# LTM8074neg_PA.net
KiCad netlist of a schematic drawn in Altium Designer
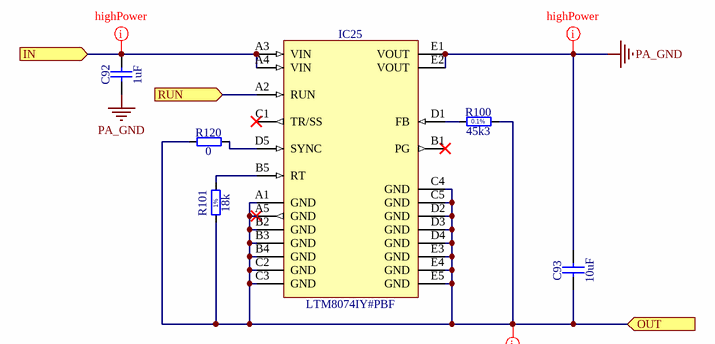
[diagram p0: LTM8074neg_PA.SchDoc]

(export (version "E")
  (design (tool "Eeschema 10.0.6"))
  (components
    (comp (ref "C92")
      (value "1uF")
      (footprint "CAPC2012X110N")
      (description "Non-polarised capacitor")
      (fields
        (field (name "PART NUMBER") "CC0805_1UF_50V_10%_X7R")
        (field (name "VOLTAGE") "50V")
        (field (name "AUTHOR") "CERN DEM JLC")
      )
      (libsource (lib "Capacitors") (part "Capacitor - non polarized"))
    )
    (comp (ref "C93")
      (value "10uF")
      (footprint "CAPC2012X95N")
      (description "Non-polarised capacitor")
      (fields
        (field (name "PART NUMBER") "CC0805_10UF_25V_10%_X5R")
        (field (name "VOLTAGE") "25V")
        (field (name "AUTHOR") "CERN DEM JLC")
      )
      (libsource (lib "Capacitors") (part "Capacitor - non polarized"))
    )
    (comp (ref "IC25")
      (value "LTM8074IY#PBF")
      (footprint "BGA25C65P5X5_400X400X198")
      (description "40VIN, 1.2A Silent Switcher µModule Regulator")
      (fields (field (name "MANUFACTURER") "LINEAR TECHNOLOGY") (field (name "AUTHOR") "CERN DEM JLC"))
      (libsource (lib "ICs And Semiconductors") (part "LTM8074"))
    )
    (comp (ref "R100")
      (value "45k3")
      (footprint "RESC1608X55N")
      (description "Resistor - 0.1%")
      (fields
        (field (name "PART NUMBER") "R0603_45K3_0.1%_0.063W_10PPM")
        (field (name "POWER") "0.063W")
        (field (name "AUTHOR") "CERN DEM JLC")
      )
      (libsource (lib "Resistors") (part "Resistor - 0.1%"))
    )
    (comp (ref "R101")
      (value "18k")
      (footprint "RESC1608X55N")
      (description "Resistor - 1%")
      (fields
        (field (name "PART NUMBER") "R0603_18K_1%_0.1W_100PPM")
        (field (name "POWER") "0.1W")
        (field (name "AUTHOR") "CERN DEM JLC")
      )
      (libsource (lib "Resistors") (part "Resistor - 1%"))
    )
    (comp (ref "R120")
      (value "0")
      (footprint "RESC1608X55N")
      (description "Resistor")
      (fields
        (field (name "PART NUMBER") "R0603_0R_JUMPER")
        (field (name "MANUFACTURER") "GENERIC")
        (field (name "AUTHOR") "CERN DEM JLC")
      )
      (libsource (lib "Resistors") (part "Resistor"))
    )
  )
  (nets
    (net (code "1") (name "/IN") (class "Default")
      (node (ref "C92") (pin "2") (pinfunction "2_2") (pintype "passive"))
      (node (ref "IC25") (pin "A3") (pinfunction "VIN_A3") (pintype "input"))
      (node (ref "IC25") (pin "A4") (pinfunction "VIN_A4") (pintype "input"))
    )
    (net (code "2") (name "/OUT") (class "Default")
      (node (ref "C93") (pin "1") (pinfunction "1_1") (pintype "passive"))
      (node (ref "IC25") (pin "A1") (pinfunction "GND_A1") (pintype "power_in"))
      (node (ref "IC25") (pin "A5") (pinfunction "GND_A5") (pintype "output"))
      (node (ref "IC25") (pin "B2") (pinfunction "GND_B2") (pintype "power_in"))
      (node (ref "IC25") (pin "B3") (pinfunction "GND_B3") (pintype "power_in"))
      (node (ref "IC25") (pin "B4") (pinfunction "GND_B4") (pintype "power_in"))
      (node (ref "IC25") (pin "C2") (pinfunction "GND_C2") (pintype "power_in"))
      (node (ref "IC25") (pin "C3") (pinfunction "GND_C3") (pintype "power_in"))
      (node (ref "IC25") (pin "C4") (pinfunction "GND_C4") (pintype "power_in"))
      (node (ref "IC25") (pin "C5") (pinfunction "GND_C5") (pintype "power_in"))
      (node (ref "IC25") (pin "D2") (pinfunction "GND_D2") (pintype "power_in"))
      (node (ref "IC25") (pin "D3") (pinfunction "GND_D3") (pintype "power_in"))
      (node (ref "IC25") (pin "D4") (pinfunction "GND_D4") (pintype "power_in"))
      (node (ref "IC25") (pin "E3") (pinfunction "GND_E3") (pintype "power_in"))
      (node (ref "IC25") (pin "E4") (pinfunction "GND_E4") (pintype "power_in"))
      (node (ref "IC25") (pin "E5") (pinfunction "GND_E5") (pintype "power_in"))
      (node (ref "R100") (pin "2") (pinfunction "2_2") (pintype "passive"))
      (node (ref "R101") (pin "1") (pinfunction "1_1") (pintype "passive"))
      (node (ref "R120") (pin "1") (pinfunction "1_1") (pintype "passive"))
    )
    (net (code "3") (name "/RUN") (class "Default")
      (node (ref "IC25") (pin "A2") (pinfunction "RUN_A2") (pintype "input"))
    )
    (net (code "4") (name "Net-(IC25-FB)") (class "Default")
      (node (ref "IC25") (pin "D1") (pinfunction "FB_D1") (pintype "input"))
      (node (ref "R100") (pin "1") (pinfunction "1_1") (pintype "passive"))
    )
    (net (code "5") (name "Net-(IC25-RT)") (class "Default")
      (node (ref "IC25") (pin "B5") (pinfunction "RT_B5") (pintype "input"))
      (node (ref "R101") (pin "2") (pinfunction "2_2") (pintype "passive"))
    )
    (net (code "6") (name "Net-(IC25-SYNC)") (class "Default")
      (node (ref "IC25") (pin "D5") (pinfunction "SYNC_D5") (pintype "input"))
      (node (ref "R120") (pin "2") (pinfunction "2_2") (pintype "passive"))
    )
    (net (code "7") (name "PA_GND") (class "Default")
      (node (ref "C92") (pin "1") (pinfunction "1_1") (pintype "passive"))
      (node (ref "C93") (pin "2") (pinfunction "2_2") (pintype "passive"))
      (node (ref "IC25") (pin "E1") (pinfunction "VOUT_E1") (pintype "power_in"))
      (node (ref "IC25") (pin "E2") (pinfunction "VOUT_E2") (pintype "power_in"))
    )
    (net (code "8") (name "unconnected-(IC25-PG-PadB1)") (class "Default")
      (node (ref "IC25") (pin "B1") (pinfunction "PG_B1") (pintype "output+no_connect"))
    )
    (net (code "9") (name "unconnected-(IC25-TR{slash}SS-PadC1)") (class "Default")
      (node (ref "IC25") (pin "C1") (pinfunction "TR/SS_C1") (pintype "output+no_connect"))
    )
  )
)
